# H-field-Near-Field-probe.net
KiCad netlist of a schematic drawn in Altium Designer
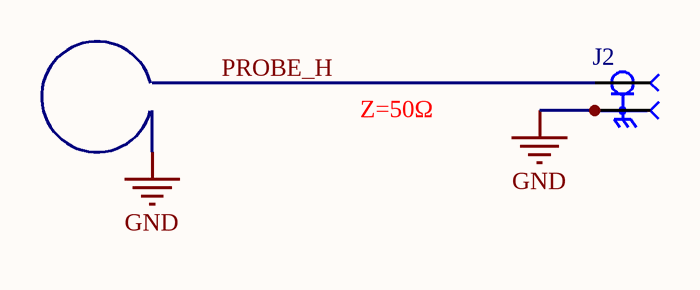
[diagram p0: H-field-Near-Field-probe.SchDoc]

(export (version "E")
  (design (tool "Eeschema 10.0.6"))
  (components
    (comp (ref "J2")
      (value "~")
      (footprint "RFSOLUTIONS_CON-SMA-EDGE-S")
      (description "SMA Connector Jack, Female Socket - Board Edge, End Launch Solder")
      (fields (field (name "MF") "RF Solutions") (field (name "DIGI-KEY_PART_NUMBER") "CON-SMA-EDGE-S-ND"))
      (libsource (lib "H-Field-Near-Field Probe") (part "CON-SMA-EDGE-S"))
    )
  )
  (nets
    (net (code "1") (name "/PROBE_H") (class "Default")
      (node (ref "J2") (pin "1") (pinfunction "1_1") (pintype "passive"))
    )
    (net (code "2") (name "GND") (class "Default")
      (node (ref "J2") (pin "G1") (pinfunction "2_G1") (pintype "passive"))
      (node (ref "J2") (pin "G2") (pinfunction "2_G2") (pintype "passive"))
      (node (ref "J2") (pin "G3") (pinfunction "2_G3") (pintype "passive"))
      (node (ref "J2") (pin "G4") (pinfunction "2_G4") (pintype "passive"))
    )
  )
)
